# Power_Switch.net
KiCad netlist of a schematic drawn in Altium Designer
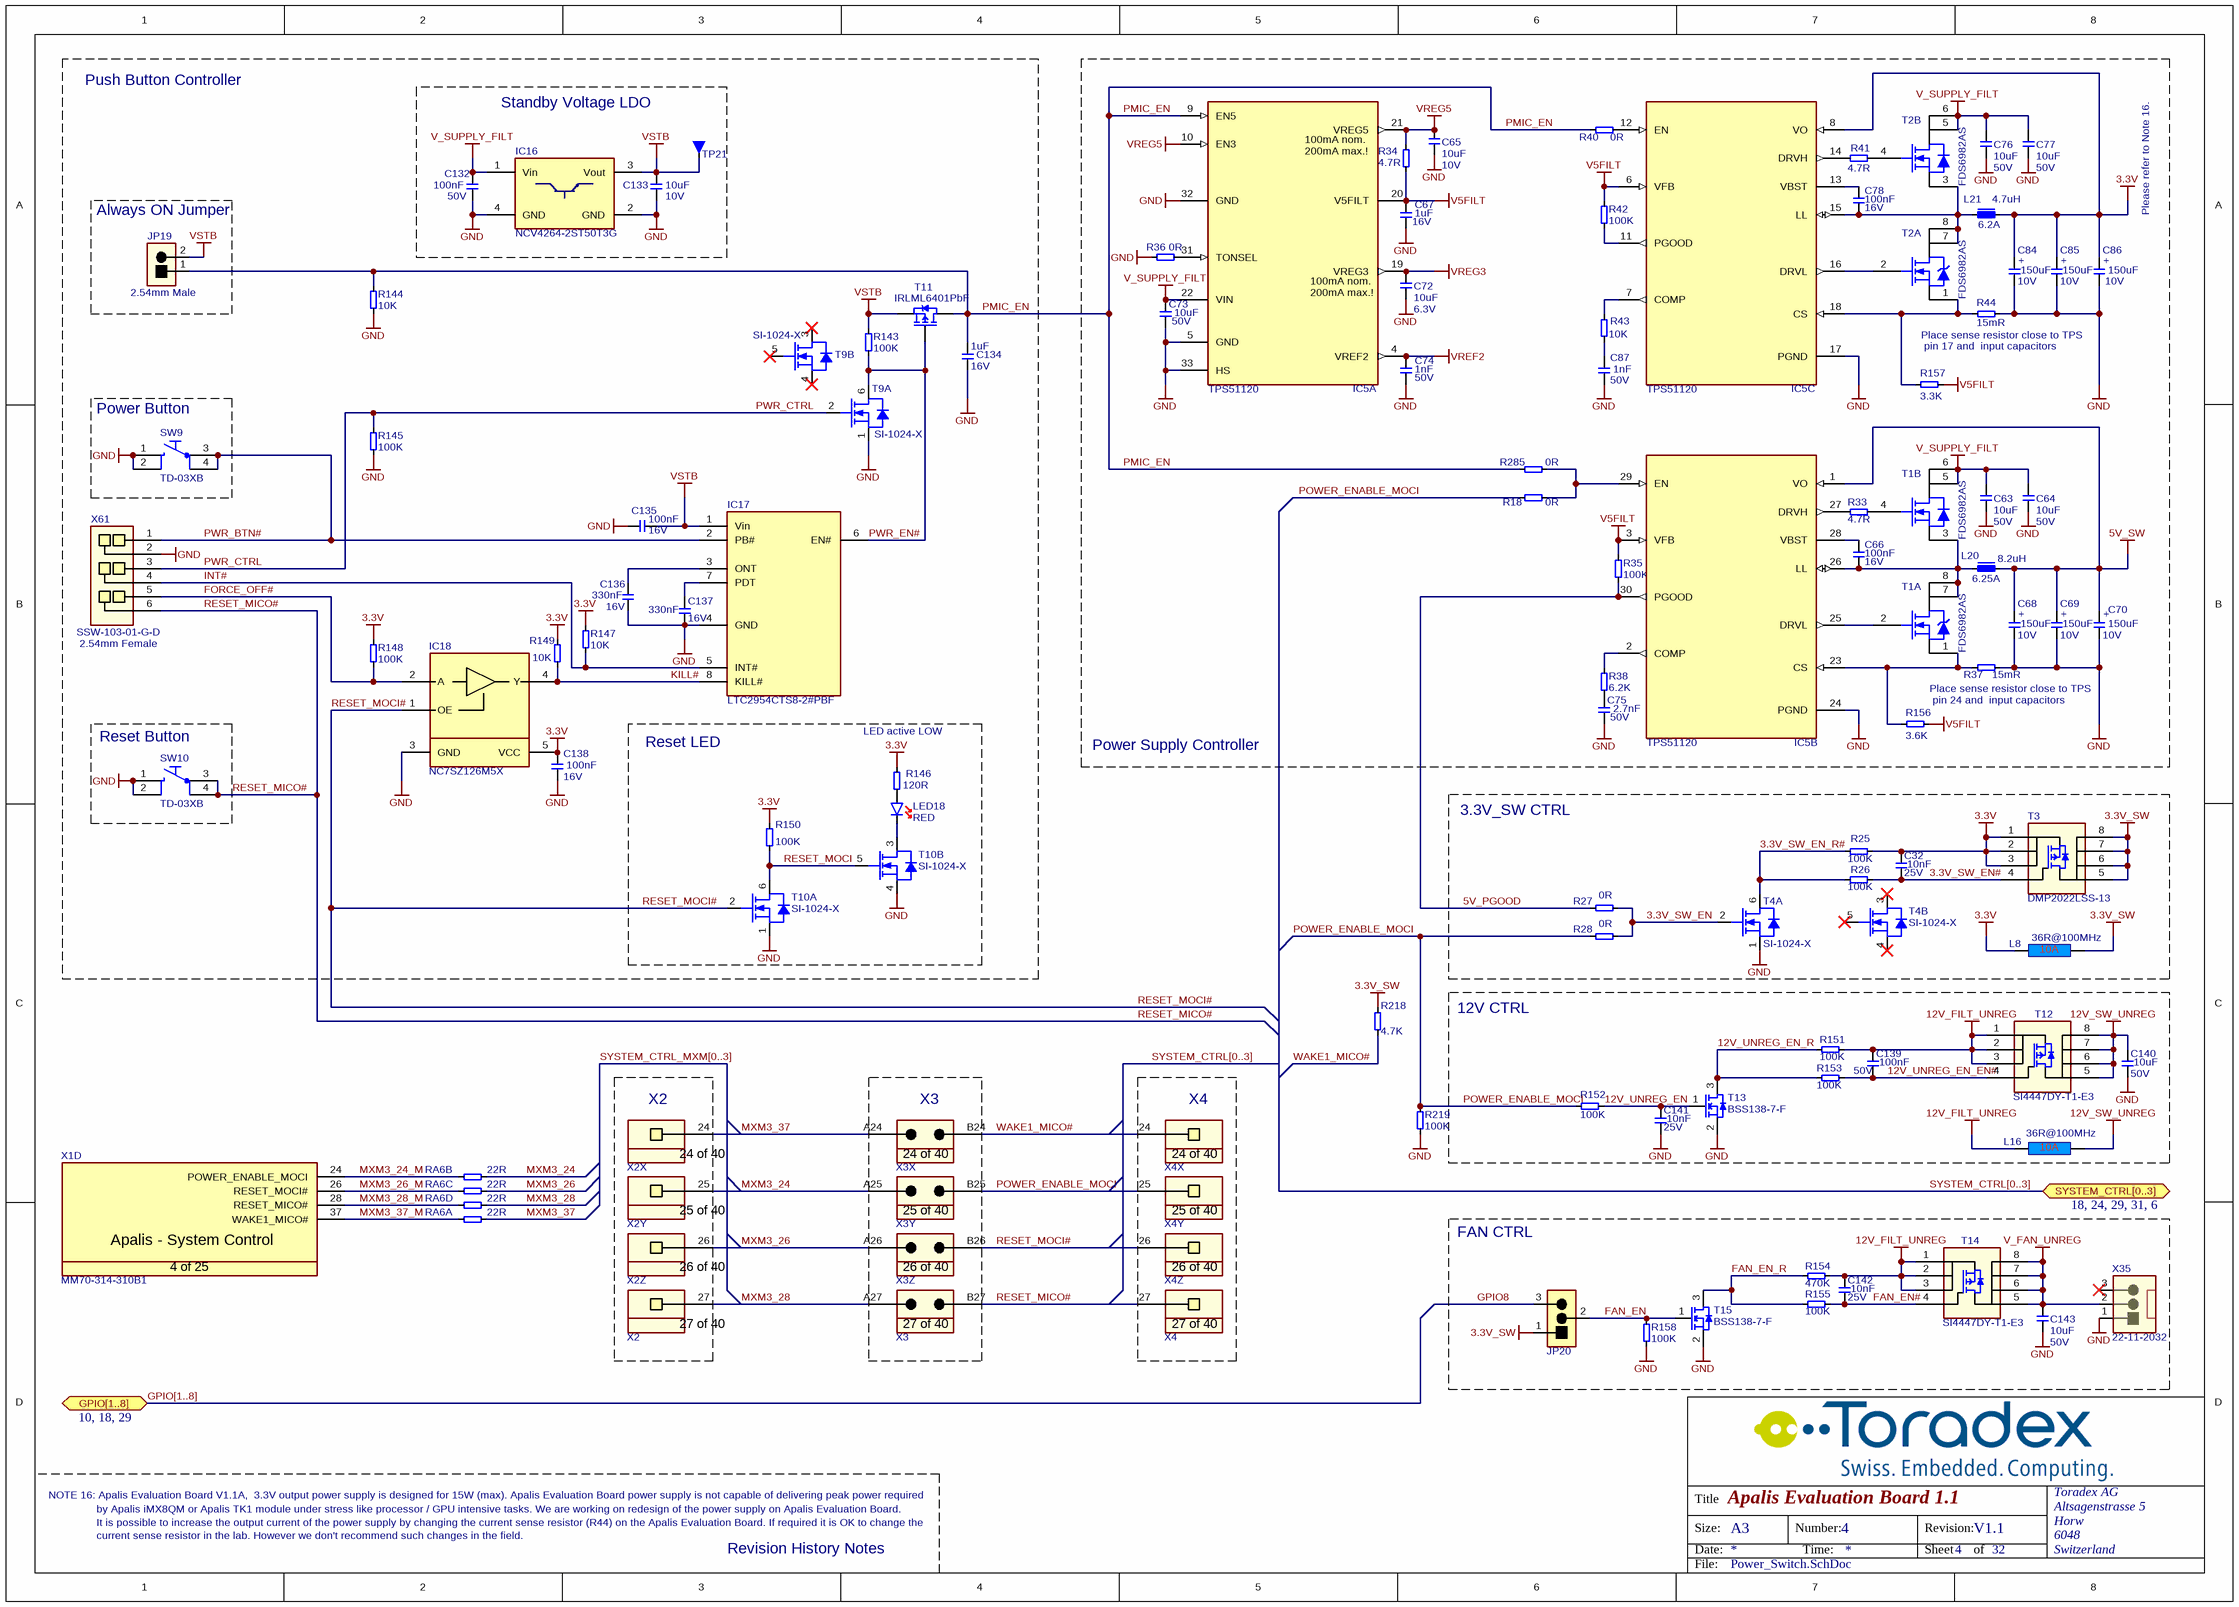
[diagram p0: Power_Switch.SchDoc]

(export (version "E")
  (design (tool "Eeschema 10.0.6"))
  (components
    (comp (ref "C32")
      (value "10nF")
      (footprint "T_CAPC0603X33N")
      (description "Capacitor Ceramic X7R 10nF 25V 10% 0603")
      (fields (field (name "TOLERANCE") "10%") (field (name "RATING") "25V"))
      (libsource (lib "Apalis Evaluation Board") (part "C-X7R-10nF-25V-10%-0603"))
    )
    (comp (ref "C63")
      (value "10uF")
      (footprint "CAPC3225X160N")
      (description "Capacitor Ceramic X5R 10uF 50V 20% 1210")
      (fields (field (name "TOLERANCE") "20%") (field (name "RATING") "50V"))
      (libsource (lib "Apalis Evaluation Board") (part "C-X5R-10uF-50V-20%-1210"))
    )
    (comp (ref "C64")
      (value "10uF")
      (footprint "CAPC3225X160N")
      (description "Capacitor Ceramic X5R 10uF 50V 20% 1210")
      (fields (field (name "TOLERANCE") "20%") (field (name "RATING") "50V"))
      (libsource (lib "Apalis Evaluation Board") (part "C-X5R-10uF-50V-20%-1210"))
    )
    (comp (ref "C65")
      (value "10uF")
      (footprint "T_CAPC0805X125N")
      (description "Capacitor Ceramic X5R 10uF 10V 20% 0805")
      (fields (field (name "TOLERANCE") "20%") (field (name "RATING") "10V"))
      (libsource (lib "Apalis Evaluation Board") (part "C-X5R-10uF-10V-20%-0805"))
    )
    (comp (ref "C66")
      (value "100nF")
      (footprint "T_CAPC0603X33N")
      (description "Capacitor Ceramic X7R 100nF 16V 10% 0603")
      (fields (field (name "TOLERANCE") "10%") (field (name "RATING") "16V"))
      (libsource (lib "Apalis Evaluation Board") (part "C-X7R-100nF-16V-10%-0603"))
    )
    (comp (ref "C67")
      (value "1uF")
      (footprint "T_CAPC0603X33N")
      (description "Capacitor Ceramic X5R 1uF 16V 20% 0603")
      (fields (field (name "TOLERANCE") "20%") (field (name "RATING") "16V"))
      (libsource (lib "Apalis Evaluation Board") (part "C-X5R-1uF-16V-20%-0603"))
    )
    (comp (ref "C68")
      (value "150uF")
      (footprint "CAPMP7343X310N")
      (description "Capacitor TA 150uF 10V 10% 7343")
      (fields (field (name "TOLERANCE") "10%") (field (name "RATING") "10V"))
      (libsource (lib "Apalis Evaluation Board") (part "C-TA-150uF-10V-10%-7343"))
    )
    (comp (ref "C69")
      (value "150uF")
      (footprint "CAPMP7343X310N")
      (description "Capacitor TA 150uF 10V 10% 7343")
      (fields (field (name "TOLERANCE") "10%") (field (name "RATING") "10V"))
      (libsource (lib "Apalis Evaluation Board") (part "C-TA-150uF-10V-10%-7343"))
    )
    (comp (ref "C70")
      (value "150uF")
      (footprint "CAPMP7343X310N")
      (description "Capacitor TA 150uF 10V 10% 7343")
      (fields (field (name "TOLERANCE") "10%") (field (name "RATING") "10V"))
      (libsource (lib "Apalis Evaluation Board") (part "C-TA-150uF-10V-10%-7343"))
    )
    (comp (ref "C72")
      (value "10uF")
      (footprint "T_CAPC0603X33N")
      (description "Capacitor Ceramic X5R 10uF 6.3V 20% 0603")
      (fields (field (name "TOLERANCE") "20%") (field (name "RATING") "6.3V"))
      (libsource (lib "Apalis Evaluation Board") (part "C-X5R-10uF-6.3V-20%-0603"))
    )
    (comp (ref "C73")
      (value "10uF")
      (footprint "CAPC3225X160N")
      (description "Capacitor Ceramic X5R 10uF 50V 20% 1210")
      (fields (field (name "TOLERANCE") "20%") (field (name "RATING") "50V"))
      (libsource (lib "Apalis Evaluation Board") (part "C-X5R-10uF-50V-20%-1210"))
    )
    (comp (ref "C74")
      (value "1nF")
      (footprint "T_CAPC0603X33N")
      (description "Capacitor Ceramic X7R 1nF 50V 10% 0603")
      (fields (field (name "TOLERANCE") "10%") (field (name "RATING") "50V"))
      (libsource (lib "Apalis Evaluation Board") (part "C-X7R-1nF-50V-10%-0603"))
    )
    (comp (ref "C75")
      (value "2.7nF")
      (footprint "CAPC1005X60N")
      (description "Capacitor Ceramic X7R 2.7nF 50V 10% 0402")
      (fields (field (name "TOLERANCE") "10%") (field (name "RATING") "50V"))
      (libsource (lib "Apalis Evaluation Board") (part "C-X7R-2.7nF-50V-10%-0402"))
    )
    (comp (ref "C76")
      (value "10uF")
      (footprint "CAPC3225X160N")
      (description "Capacitor Ceramic X5R 10uF 50V 20% 1210")
      (fields (field (name "TOLERANCE") "20%") (field (name "RATING") "50V"))
      (libsource (lib "Apalis Evaluation Board") (part "C-X5R-10uF-50V-20%-1210"))
    )
    (comp (ref "C77")
      (value "10uF")
      (footprint "CAPC3225X160N")
      (description "Capacitor Ceramic X5R 10uF 50V 20% 1210")
      (fields (field (name "TOLERANCE") "20%") (field (name "RATING") "50V"))
      (libsource (lib "Apalis Evaluation Board") (part "C-X5R-10uF-50V-20%-1210"))
    )
    (comp (ref "C78")
      (value "100nF")
      (footprint "T_CAPC0603X33N")
      (description "Capacitor Ceramic X7R 100nF 16V 10% 0603")
      (fields (field (name "TOLERANCE") "10%") (field (name "RATING") "16V"))
      (libsource (lib "Apalis Evaluation Board") (part "C-X7R-100nF-16V-10%-0603"))
    )
    (comp (ref "C84")
      (value "150uF")
      (footprint "CAPMP7343X310N")
      (description "Capacitor TA 150uF 10V 10% 7343")
      (fields (field (name "TOLERANCE") "10%") (field (name "RATING") "10V"))
      (libsource (lib "Apalis Evaluation Board") (part "C-TA-150uF-10V-10%-7343"))
    )
    (comp (ref "C85")
      (value "150uF")
      (footprint "CAPMP7343X310N")
      (description "Capacitor TA 150uF 10V 10% 7343")
      (fields (field (name "TOLERANCE") "10%") (field (name "RATING") "10V"))
      (libsource (lib "Apalis Evaluation Board") (part "C-TA-150uF-10V-10%-7343"))
    )
    (comp (ref "C86")
      (value "150uF")
      (footprint "CAPMP7343X310N")
      (description "Capacitor TA 150uF 10V 10% 7343")
      (fields (field (name "TOLERANCE") "10%") (field (name "RATING") "10V"))
      (libsource (lib "Apalis Evaluation Board") (part "C-TA-150uF-10V-10%-7343"))
    )
    (comp (ref "C87")
      (value "1nF")
      (footprint "T_CAPC0603X33N")
      (description "Capacitor Ceramic X7R 1nF 50V 10% 0603")
      (fields (field (name "TOLERANCE") "10%") (field (name "RATING") "50V"))
      (libsource (lib "Apalis Evaluation Board") (part "C-X7R-1nF-50V-10%-0603"))
    )
    (comp (ref "C132")
      (value "100nF")
      (footprint "T_CAPC0603X33N")
      (description "Capacitor Ceramic X7R 100nF 50V 20% 0603")
      (fields (field (name "TOLERANCE") "20%") (field (name "RATING") "50V"))
      (libsource (lib "Apalis Evaluation Board") (part "C-X7R-100nF-50V-20%-0603"))
    )
    (comp (ref "C133")
      (value "10uF")
      (footprint "T_CAPC0805X125N")
      (description "Capacitor Ceramic X5R 10uF 10V 20% 0805")
      (fields (field (name "TOLERANCE") "20%") (field (name "RATING") "10V"))
      (libsource (lib "Apalis Evaluation Board") (part "C-X5R-10uF-10V-20%-0805"))
    )
    (comp (ref "C134")
      (value "1uF")
      (footprint "T_CAPC0603X33N")
      (description "Capacitor Ceramic X5R 1uF 16V 20% 0603")
      (fields (field (name "TOLERANCE") "20%") (field (name "RATING") "16V"))
      (libsource (lib "Apalis Evaluation Board") (part "C-X5R-1uF-16V-20%-0603"))
    )
    (comp (ref "C135")
      (value "100nF")
      (footprint "T_CAPC0603X33N")
      (description "Capacitor Ceramic X7R 100nF 16V 10% 0603")
      (fields (field (name "TOLERANCE") "10%") (field (name "RATING") "16V"))
      (libsource (lib "Apalis Evaluation Board") (part "C-X7R-100nF-16V-10%-0603"))
    )
    (comp (ref "C136")
      (value "330nF")
      (footprint "T_CAPC0805X125N")
      (description "Capacitor Ceramic X7R 330nF 16V 10% 0805")
      (fields (field (name "TOLERANCE") "10%") (field (name "RATING") "16V"))
      (libsource (lib "Apalis Evaluation Board") (part "C-X7R-330nF-16V-10%-0805"))
    )
    (comp (ref "C137")
      (value "330nF")
      (footprint "T_CAPC0805X125N")
      (description "Capacitor Ceramic X7R 330nF 16V 10% 0805")
      (fields (field (name "TOLERANCE") "10%") (field (name "RATING") "16V"))
      (libsource (lib "Apalis Evaluation Board") (part "C-X7R-330nF-16V-10%-0805"))
    )
    (comp (ref "C138")
      (value "100nF")
      (footprint "T_CAPC0603X33N")
      (description "Capacitor Ceramic X7R 100nF 16V 10% 0603")
      (fields (field (name "TOLERANCE") "10%") (field (name "RATING") "16V"))
      (libsource (lib "Apalis Evaluation Board") (part "C-X7R-100nF-16V-10%-0603"))
    )
    (comp (ref "C139")
      (value "100nF")
      (footprint "T_CAPC0603X33N")
      (description "Capacitor Ceramic X7R 100nF 50V 20% 0603")
      (fields (field (name "TOLERANCE") "20%") (field (name "RATING") "50V"))
      (libsource (lib "Apalis Evaluation Board") (part "C-X7R-100nF-50V-20%-0603"))
    )
    (comp (ref "C140")
      (value "10uF")
      (footprint "CAPC3225X160N")
      (description "Capacitor Ceramic X5R 10uF 50V 20% 1210")
      (fields (field (name "TOLERANCE") "20%") (field (name "RATING") "50V"))
      (libsource (lib "Apalis Evaluation Board") (part "C-X5R-10uF-50V-20%-1210"))
    )
    (comp (ref "C141")
      (value "10nF")
      (footprint "T_CAPC0603X33N")
      (description "Capacitor Ceramic X7R 10nF 25V 10% 0603")
      (fields (field (name "TOLERANCE") "10%") (field (name "RATING") "25V"))
      (libsource (lib "Apalis Evaluation Board") (part "C-X7R-10nF-25V-10%-0603"))
    )
    (comp (ref "C142")
      (value "10nF")
      (footprint "T_CAPC0603X33N")
      (description "Capacitor Ceramic X7R 10nF 25V 10% 0603")
      (fields (field (name "TOLERANCE") "10%") (field (name "RATING") "25V"))
      (libsource (lib "Apalis Evaluation Board") (part "C-X7R-10nF-25V-10%-0603"))
    )
    (comp (ref "C143")
      (value "10uF")
      (footprint "CAPC3225X160N")
      (description "Capacitor Ceramic X5R 10uF 50V 20% 1210")
      (fields (field (name "TOLERANCE") "20%") (field (name "RATING") "50V"))
      (libsource (lib "Apalis Evaluation Board") (part "C-X5R-10uF-50V-20%-1210"))
    )
    (comp (ref "IC5")
      (value "TPS51120")
      (footprint "QFN50P500X500X100-33N")
      (description "Power Supply Controller")
      (fields (field (name "MANUFACTURER PART NO.") "TPS51120"))
      (libsource (lib "Apalis Evaluation Board") (part "IC-TI-TPS51120"))
    )
    (comp (ref "IC16")
      (value "NCV4264-2ST50T3G")
      (footprint "T_ON_NCV4264-2ST50T3G")
      (description "NCV4264-2ST50T3G LDO Regulator")
      (fields (field (name "MANUFACTURER PART NO.") "NCV4264-2ST50T3G"))
      (libsource (lib "Apalis Evaluation Board") (part "IC-ON-NCV4264-2ST50T3G"))
    )
    (comp (ref "IC17")
      (value "LTC2954CTS8-2#PBF")
      (footprint "T_LINEAR_LTC2954CTS8-2#PBF")
      (description "Push Button On/Off Controller")
      (fields (field (name "MANUFACTURER PART NO.") "LTC2954CTS8-2#PBF"))
      (libsource (lib "Apalis Evaluation Board") (part "IC-LIN-LTC2954CTS8-2#PBF"))
    )
    (comp (ref "IC18")
      (value "NC7SZ126M5X")
      (footprint "SOT95P279X142-5N")
      (description "NC7SZ126M5X  Buffer Three-State Output")
      (fields (field (name "MANUFACTURER PART NO.") "NC7SZ126M5X"))
      (libsource (lib "Apalis Evaluation Board") (part "IC-FAR-NC7SZ126M5X"))
    )
    (comp (ref "JP19")
      (value "TSW-101-07-G-D")
      (footprint "T_Samtec_TSW-101-07-G-D")
      (description "Header male, 1x2 Pins, 2.54 mm pitch")
      (libsource (lib "Apalis Evaluation Board") (part "CON-Samtec-TSW-101-07-G-D"))
    )
    (comp (ref "JP20")
      (value "826936-3")
      (footprint "T_TYCO_826936-3")
      (description "Jumper, 3-Pin")
      (libsource (lib "Apalis Evaluation Board") (part "CON-Tyco-826936-3-1X3-2.54mm-JP_1"))
    )
    (comp (ref "L8")
      (value "36R@100MHz")
      (footprint "T_Laird_35F0121-0SR-10")
      (description "Power Supply FB 10A")
      (fields (field (name "TOLERANCE") "25%"))
      (libsource (lib "Apalis Evaluation Board") (part "L-Laird-35F0121-0SR-10-10A-25%"))
    )
    (comp (ref "L16")
      (value "36R@100MHz")
      (footprint "T_Laird_35F0121-0SR-10")
      (description "Power Supply FB 10A")
      (fields (field (name "TOLERANCE") "25%"))
      (libsource (lib "Apalis Evaluation Board") (part "L-Laird-35F0121-0SR-10-10A-25%"))
    )
    (comp (ref "L20")
      (value "8.2uH")
      (footprint "T_INDM120120X80N")
      (description "Inductance 8.2uH 6.25A 20%")
      (fields
        (field (name "TOLERANCE") "20%")
        (field (name "MANUFACTURER PART NO.") "744771008")
        (field (name "RATING") "6.25A")
      )
      (libsource (lib "Apalis Evaluation Board") (part "L-Wurth-744771008-8.2uH-6.25A-20%"))
    )
    (comp (ref "L21")
      (value "4.7uH")
      (footprint "T_INDM102102X45N")
      (description "Inductance 4.7uH 6.2A 20%")
      (fields
        (field (name "TOLERANCE") "20%")
        (field (name "MANUFACTURER PART NO.") "7447797470")
        (field (name "RATING") "6.2A")
      )
      (libsource (lib "Apalis Evaluation Board") (part "L-Wurth-7447797470-4.7uH-6.2A-20%"))
    )
    (comp (ref "LED18")
      (value "LS T670-K1L2-1")
      (footprint "T_Osram_T670_RED")
      (description "LED red, Osram LS T670-K1L2-1")
      (fields (field (name "COLOR") "RED"))
      (libsource (lib "Apalis Evaluation Board") (part "LED-Osram-LS T670-K1L2-1"))
    )
    (comp (ref "R18")
      (value "0R")
      (footprint "T_RESC0603X30N")
      (description "Resistor 0 ohm 63mW 1% 0603")
      (fields (field (name "TOLERANCE") "1%"))
      (libsource (lib "Apalis Evaluation Board") (part "R-0R-63mW-1%-0603"))
    )
    (comp (ref "R25")
      (value "100K")
      (footprint "T_RESC0603X30N")
      (description "Resistor 100 Kohm 63mW 5% 0603")
      (fields (field (name "TOLERANCE") "5%"))
      (libsource (lib "") (part "R-100KR-63mW-5%-0603_1"))
    )
    (comp (ref "R26")
      (value "100K")
      (footprint "T_RESC0603X30N")
      (description "Resistor 100 Kohm 63mW 5% 0603")
      (fields (field (name "TOLERANCE") "5%"))
      (libsource (lib "") (part "R-100KR-63mW-5%-0603_1"))
    )
    (comp (ref "R27")
      (value "0R")
      (footprint "T_RESC0603X30N")
      (description "Resistor 0 ohm 63mW 1% 0603")
      (fields (field (name "TOLERANCE") "1%"))
      (libsource (lib "Apalis Evaluation Board") (part "R-0R-63mW-1%-0603"))
    )
    (comp (ref "R28")
      (value "0R")
      (footprint "T_RESC0603X30N")
      (description "Resistor 0 ohm 63mW 1% 0603")
      (fields (field (name "TOLERANCE") "1%"))
      (libsource (lib "Apalis Evaluation Board") (part "R-0R-63mW-1%-0603"))
    )
    (comp (ref "R33")
      (value "4.7R")
      (footprint "RESC1005X40N")
      (description "Resistor 4.7 ohm 63mW 5% 0402")
      (fields (field (name "TOLERANCE") "5%"))
      (libsource (lib "Apalis Evaluation Board") (part "R-4.7R-63mW-5%-0402"))
    )
    (comp (ref "R34")
      (value "4.7R")
      (footprint "RESC1005X40N")
      (description "Resistor 4.7 ohm 63mW 5% 0402")
      (fields (field (name "TOLERANCE") "5%"))
      (libsource (lib "Apalis Evaluation Board") (part "R-4.7R-63mW-5%-0402"))
    )
    (comp (ref "R35")
      (value "100K")
      (footprint "T_RESC0603X30N")
      (description "Resistor 100 Kohm 63mW 5% 0603")
      (fields (field (name "TOLERANCE") "5%"))
      (libsource (lib "") (part "R-100KR-63mW-5%-0603_1"))
    )
    (comp (ref "R36")
      (value "0R")
      (footprint "T_RESC0603X30N")
      (description "Resistor 0 ohm 63mW 1% 0603")
      (fields (field (name "TOLERANCE") "1%"))
      (libsource (lib "Apalis Evaluation Board") (part "R-0R-63mW-1%-0603"))
    )
    (comp (ref "R37")
      (value "15mR")
      (footprint "RESC3316X76N")
      (description "Resistor 15 mohm 250mW 1% 1206")
      (fields (field (name "TOLERANCE") "1%"))
      (libsource (lib "Apalis Evaluation Board") (part "R-15mR-250mW-1%-1206"))
    )
    (comp (ref "R38")
      (value "6.2K")
      (footprint "RESC1005X40N")
      (description "Resistor 6.2 Kohm 63mW 1% 0402")
      (fields (field (name "TOLERANCE") "1%"))
      (libsource (lib "Apalis Evaluation Board") (part "R-6.2KR-63mW-1%-0402"))
    )
    (comp (ref "R40")
      (value "0R")
      (footprint "T_RESC0603X30N")
      (description "Resistor 0 ohm 63mW 1% 0603")
      (fields (field (name "TOLERANCE") "1%"))
      (libsource (lib "Apalis Evaluation Board") (part "R-0R-63mW-1%-0603"))
    )
    (comp (ref "R41")
      (value "4.7R")
      (footprint "RESC1005X40N")
      (description "Resistor 4.7 ohm 63mW 5% 0402")
      (fields (field (name "TOLERANCE") "5%"))
      (libsource (lib "Apalis Evaluation Board") (part "R-4.7R-63mW-5%-0402"))
    )
    (comp (ref "R42")
      (value "100K")
      (footprint "T_RESC0603X30N")
      (description "Resistor 100 Kohm 63mW 5% 0603")
      (fields (field (name "TOLERANCE") "5%"))
      (libsource (lib "") (part "R-100KR-63mW-5%-0603_1"))
    )
    (comp (ref "R43")
      (value "10K")
      (footprint "RESC1005X40N")
      (description "Resistor 10 Kohm 63mW 1% 0402")
      (fields (field (name "TOLERANCE") "1%"))
      (libsource (lib "Apalis Evaluation Board") (part "R-10KR-63mW-1%-0402"))
    )
    (comp (ref "R44")
      (value "15mR")
      (footprint "RESC3316X76N")
      (description "Resistor 15 mohm 250mW 1% 1206")
      (fields (field (name "TOLERANCE") "1%"))
      (libsource (lib "Apalis Evaluation Board") (part "R-15mR-250mW-1%-1206"))
    )
    (comp (ref "R143")
      (value "100K")
      (footprint "T_RESC0603X30N")
      (description "Resistor 100 Kohm 63mW 5% 0603")
      (fields (field (name "TOLERANCE") "5%"))
      (libsource (lib "") (part "R-100KR-63mW-5%-0603_1"))
    )
    (comp (ref "R144")
      (value "10K")
      (footprint "T_RESC0603X30N")
      (description "Resistor 10 Kohm 63mW 5% 0603")
      (fields (field (name "TOLERANCE") "5%"))
      (libsource (lib "Apalis Evaluation Board") (part "R-10KR-63mW-5%-0603"))
    )
    (comp (ref "R145")
      (value "100K")
      (footprint "T_RESC0603X30N")
      (description "Resistor 100 Kohm 63mW 5% 0603")
      (fields (field (name "TOLERANCE") "5%"))
      (libsource (lib "") (part "R-100KR-63mW-5%-0603_1"))
    )
    (comp (ref "R146")
      (value "120R")
      (footprint "T_RESC0603X30N")
      (description "Resistor 120 ohm 63mW 5% 0603")
      (fields (field (name "TOLERANCE") "5%"))
      (libsource (lib "Apalis Evaluation Board") (part "R-120R-63mW-5%-0603"))
    )
    (comp (ref "R147")
      (value "10K")
      (footprint "T_RESC0603X30N")
      (description "Resistor 10 Kohm 63mW 5% 0603")
      (fields (field (name "TOLERANCE") "5%"))
      (libsource (lib "Apalis Evaluation Board") (part "R-10KR-63mW-5%-0603"))
    )
    (comp (ref "R148")
      (value "100K")
      (footprint "T_RESC0603X30N")
      (description "Resistor 100 Kohm 63mW 5% 0603")
      (fields (field (name "TOLERANCE") "5%"))
      (libsource (lib "") (part "R-100KR-63mW-5%-0603_1"))
    )
    (comp (ref "R149")
      (value "10K")
      (footprint "T_RESC0603X30N")
      (description "Resistor 10 Kohm 63mW 5% 0603")
      (fields (field (name "TOLERANCE") "5%"))
      (libsource (lib "Apalis Evaluation Board") (part "R-10KR-63mW-5%-0603"))
    )
    (comp (ref "R150")
      (value "100K")
      (footprint "T_RESC0603X30N")
      (description "Resistor 100 Kohm 63mW 5% 0603")
      (fields (field (name "TOLERANCE") "5%"))
      (libsource (lib "") (part "R-100KR-63mW-5%-0603_1"))
    )
    (comp (ref "R151")
      (value "100K")
      (footprint "T_RESC0603X30N")
      (description "Resistor 100 Kohm 63mW 5% 0603")
      (fields (field (name "TOLERANCE") "5%"))
      (libsource (lib "") (part "R-100KR-63mW-5%-0603_1"))
    )
    (comp (ref "R152")
      (value "100K")
      (footprint "T_RESC0603X30N")
      (description "Resistor 100 Kohm 63mW 5% 0603")
      (fields (field (name "TOLERANCE") "5%"))
      (libsource (lib "") (part "R-100KR-63mW-5%-0603_1"))
    )
    (comp (ref "R153")
      (value "100K")
      (footprint "T_RESC0603X30N")
      (description "Resistor 100 Kohm 63mW 5% 0603")
      (fields (field (name "TOLERANCE") "5%"))
      (libsource (lib "") (part "R-100KR-63mW-5%-0603_1"))
    )
    (comp (ref "R154")
      (value "470K")
      (footprint "T_RESC0603X30N")
      (description "Resistor 470 Kohm 63mW 5% 0603")
      (fields (field (name "TOLERANCE") "5%"))
      (libsource (lib "Apalis Evaluation Board") (part "R-470KR-63mW-5%-0603"))
    )
    (comp (ref "R155")
      (value "100K")
      (footprint "T_RESC0603X30N")
      (description "Resistor 100 Kohm 63mW 5% 0603")
      (fields (field (name "TOLERANCE") "5%"))
      (libsource (lib "") (part "R-100KR-63mW-5%-0603_1"))
    )
    (comp (ref "R156")
      (value "3.6K")
      (footprint "T_RESC0603X30N")
      (description "Resistor 3.6 Kohm 63mW 1% 0603")
      (fields (field (name "TOLERANCE") "1%"))
      (libsource (lib "Apalis Evaluation Board") (part "R-3.6KR-63mW-1%-0603"))
    )
    (comp (ref "R157")
      (value "3.3K")
      (footprint "T_RESC0603X30N")
      (description "Resistor 3.3 Kohm 63mW 1% 0603")
      (fields (field (name "TOLERANCE") "1%"))
      (libsource (lib "Apalis Evaluation Board") (part "R-3.3KR-63mW-1%-0603"))
    )
    (comp (ref "R158")
      (value "100K")
      (footprint "T_RESC0603X30N")
      (description "Resistor 100 Kohm 63mW 5% 0603")
      (fields (field (name "TOLERANCE") "5%"))
      (libsource (lib "") (part "R-100KR-63mW-5%-0603_1"))
    )
    (comp (ref "R218")
      (value "4.7K")
      (footprint "t_RESC0603X30N")
      (description "Resistor 4.7 Kohm 63mW 5% 0603")
      (fields (field (name "TOLERANCE") "5%"))
      (libsource (lib "Apalis Evaluation Board") (part "R-4.7kR-63mW-5%-0603"))
    )
    (comp (ref "R219")
      (value "100K")
      (footprint "T_RESC0603X30N")
      (description "Resistor 100 Kohm 63mW 5% 0603")
      (fields (field (name "TOLERANCE") "5%"))
      (libsource (lib "Apalis Evaluation Board") (part "R-100KR-63mW-5%-0603"))
    )
    (comp (ref "R285")
      (value "0R")
      (footprint "T_RESC0603X30N")
      (description "Resistor 0 ohm 63mW 1% 0603")
      (fields (field (name "TOLERANCE") "1%"))
      (libsource (lib "Apalis Evaluation Board") (part "R-0R-63mW-1%-0603"))
    )
    (comp (ref "RA6")
      (value "22R")
      (footprint "T_Resistor_Array_X4")
      (description "Resistor Array 22 R 63mW 5% 1206")
      (fields (field (name "TOLERANCE") "5%"))
      (libsource (lib "Apalis Evaluation Board") (part "RA-22R-63mW-5%-1206-div"))
    )
    (comp (ref "SW9")
      (value "TD-03XB")
      (footprint "T_WMF_TD-03XB")
      (description "Push Button")
      (libsource (lib "Apalis Evaluation Board") (part "SW-WMF-TD-03XB"))
    )
    (comp (ref "SW10")
      (value "TD-03XB")
      (footprint "T_WMF_TD-03XB")
      (description "Push Button")
      (libsource (lib "Apalis Evaluation Board") (part "SW-WMF-TD-03XB"))
    )
    (comp (ref "T1")
      (value "FDS6982AS")
      (footprint "SOIC127P600X173-8N")
      (description "N-Channel PowerTrench SyncFET")
      (fields (field (name "MANUFACTURER PART NO.") "FDS6982AS"))
      (libsource (lib "Apalis Evaluation Board") (part "T-Fairchild-FDS6982AS-N"))
    )
    (comp (ref "T2")
      (value "FDS6982AS")
      (footprint "SOIC127P600X173-8N")
      (description "N-Channel PowerTrench SyncFET")
      (fields (field (name "MANUFACTURER PART NO.") "FDS6982AS"))
      (libsource (lib "") (part "T-Fairchild-FDS6982AS-N_1"))
    )
    (comp (ref "T3")
      (value "DMP2022LSS-13")
      (footprint "SOIC127P600X173-8N")
      (description "p-channel MOSFET, DMP2022LSS-13")
      (fields (field (name "MANUFACTURER PART NO.") "DMP2022LSS-13"))
      (libsource (lib "Apalis Evaluation Board") (part "T-Diodes-DMP2022LSS-13-8-SOIC"))
    )
    (comp (ref "T4")
      (value "T-Vishay-SI-1024X-N")
      (footprint "SOTFL50P160X60-6N")
      (description "Dual N-Channel 20V (D-S)  MOSFET")
      (fields (field (name "MANUFACTURER PART NO.") "SI-1024-X"))
      (libsource (lib "Apalis Evaluation Board") (part "T-Vishay-SI-1024X-N"))
    )
    (comp (ref "T9")
      (value "T-Vishay-SI-1024X-N")
      (footprint "SOTFL50P160X60-6N")
      (description "Dual N-Channel 20V (D-S)  MOSFET")
      (fields (field (name "MANUFACTURER PART NO.") "SI-1024-X"))
      (libsource (lib "Apalis Evaluation Board") (part "T-Vishay-SI-1024X-N"))
    )
    (comp (ref "T10")
      (value "T-Vishay-SI-1024X-N")
      (footprint "SOTFL50P160X60-6N")
      (description "Dual N-Channel 20V (D-S)  MOSFET")
      (fields (field (name "MANUFACTURER PART NO.") "SI-1024-X"))
      (libsource (lib "Apalis Evaluation Board") (part "T-Vishay-SI-1024X-N"))
    )
    (comp (ref "T11")
      (value "IRLML6401PbF")
      (footprint "SOT95P237X112-3N")
      (description "p-channel MOSFET, IRLML6401PbF")
      (libsource (lib "Apalis Evaluation Board") (part "T-IR-IRLML6401PbF-SOT-23"))
    )
    (comp (ref "T12")
      (value "SI4447DY-T1-E3")
      (footprint "SOIC127P600X173-8N")
      (description "p-channel MOSFET, SI4447DY-T1-E3")
      (fields (field (name "MANUFACTURER PART NO.") "SI4447DY-T1-E3"))
      (libsource (lib "Apalis Evaluation Board") (part "T-Vishay-SI4447DY-T1-E3"))
    )
    (comp (ref "T13")
      (value "BSS138-7-F")
      (footprint "SOT95P237X112-3N")
      (description "N-channel MOSFET, BSS138-7-F")
      (fields (field (name "MANUFACTURER PART NO.") "BSS138-7-F"))
      (libsource (lib "Apalis Evaluation Board") (part "T-Diodes-BSS138-7-F"))
    )
    (comp (ref "T14")
      (value "SI4447DY-T1-E3")
      (footprint "SOIC127P600X173-8N")
      (description "p-channel MOSFET, SI4447DY-T1-E3")
      (fields (field (name "MANUFACTURER PART NO.") "SI4447DY-T1-E3"))
      (libsource (lib "Apalis Evaluation Board") (part "T-Vishay-SI4447DY-T1-E3"))
    )
    (comp (ref "T15")
      (value "BSS138-7-F")
      (footprint "SOT95P237X112-3N")
      (description "N-channel MOSFET, BSS138-7-F")
      (fields (field (name "MANUFACTURER PART NO.") "BSS138-7-F"))
      (libsource (lib "Apalis Evaluation Board") (part "T-Diodes-BSS138-7-F"))
    )
    (comp (ref "TP21")
      (value "Testpin")
      (footprint "T_TP-THT")
      (description "Testpin TH")
      (libsource (lib "Apalis Evaluation Board") (part "Testpin"))
    )
    (comp (ref "X1")
      (value "CON-JAE-MM70-314-310B1-314-0.5mm")
      (footprint "T_JAE_MM70-314-310B1")
      (description "MXM3 Connector")
      (fields (field (name "MANUFACTURER PART NO.") "MM70-314-310B1"))
      (libsource (lib "Apalis Evaluation Board") (part "CON-JAE-MM70-314-310B1-314-0.5mm"))
    )
    (comp (ref "X2")
      (value "SSW-110-01-G-S")
      (footprint "T_Samtec_SSW-110-01-G-S")
      (description "Receptacle Female Socket 1x40 pin 2.54mm pitch")
      (libsource (lib "Apalis Evaluation Board") (part "CON-Samtec-SSW-110-01-G-S"))
    )
    (comp (ref "X3")
      (value "TSW-110-07-G-D")
      (footprint "T_Samtec_TSW-110-07-G-D")
      (description "Header 2x40 pin 2.54mm pitch")
      (libsource (lib "Apalis Evaluation Board") (part "CON-Samtec-TSW-110-07-G-D"))
    )
    (comp (ref "X4")
      (value "SSW-110-01-G-S")
      (footprint "T_Samtec_SSW-110-01-G-S")
      (description "Receptacle Female Socket 1x40 pin 2.54mm pitch")
      (libsource (lib "") (part "CON-Samtec-SSW-110-01-G-S_1"))
    )
    (comp (ref "X35")
      (value "22-11-2032")
      (footprint "T_MOLEX_22-11-2032")
      (description "Header with Friction Lock")
      (fields (field (name "MANUFACTURER PART NO.") "22-11-2032"))
      (libsource (lib "Apalis Evaluation Board") (part "CON-Molex-22-11-2032"))
    )
    (comp (ref "X61")
      (value "TSW-103-01-G-D")
      (footprint "T_Samtec_SSW-103-01-G-D")
      (description "Receptacle Female Socket, 2x3 Pins, 2.54mm pitch")
      (fields (field (name "MANUFACTURER PART NO.") "SSW-103-01-G-D"))
      (libsource (lib "Apalis Evaluation Board") (part "CON-Samtec-SSW-103-01-G-D"))
    )
  )
  (nets
    (net (code "16") (name "/3.3V_SW_EN") (class "Default")
      (node (ref "R27") (pin "1") (pinfunction "1_1") (pintype "passive"))
      (node (ref "R28") (pin "2") (pinfunction "2_2") (pintype "passive"))
      (node (ref "T4") (pin "2") (pinfunction "G_2") (pintype "passive"))
    )
    (net (code "17") (name "/3.3V_SW_EN#") (class "Default")
      (node (ref "C32") (pin "1") (pinfunction "1_1") (pintype "passive"))
      (node (ref "R26") (pin "1") (pinfunction "1_1") (pintype "passive"))
      (node (ref "T3") (pin "4") (pinfunction "G_4") (pintype "passive"))
    )
    (net (code "18") (name "/3.3V_SW_EN_R#") (class "Default")
      (node (ref "R25") (pin "2") (pinfunction "2_2") (pintype "passive"))
      (node (ref "R26") (pin "2") (pinfunction "2_2") (pintype "passive"))
      (node (ref "T4") (pin "6") (pinfunction "D_6") (pintype "passive"))
    )
    (net (code "19") (name "/5V_PGOOD") (class "Default")
      (node (ref "IC5") (pin "30") (pinfunction "PGOOD_30") (pintype "output"))
      (node (ref "R27") (pin "2") (pinfunction "2_2") (pintype "passive"))
      (node (ref "R35") (pin "1") (pinfunction "1_1") (pintype "passive"))
    )
    (net (code "20") (name "/12V_UNREG_EN") (class "Default")
      (node (ref "C141") (pin "2") (pinfunction "2_2") (pintype "passive"))
      (node (ref "R152") (pin "2") (pinfunction "2_2") (pintype "passive"))
      (node (ref "T13") (pin "1") (pinfunction "1_1") (pintype "passive"))
    )
    (net (code "21") (name "/12V_UNREG_EN_EN#") (class "Default")
      (node (ref "C139") (pin "1") (pinfunction "1_1") (pintype "passive"))
      (node (ref "R153") (pin "2") (pinfunction "2_2") (pintype "passive"))
      (node (ref "T12") (pin "4") (pinfunction "G_4") (pintype "passive"))
    )
    (net (code "22") (name "/12V_UNREG_EN_R") (class "Default")
      (node (ref "R151") (pin "1") (pinfunction "1_1") (pintype "passive"))
      (node (ref "R153") (pin "1") (pinfunction "1_1") (pintype "passive"))
      (node (ref "T13") (pin "3") (pinfunction "3_3") (pintype "passive"))
    )
    (net (code "23") (name "/FAN_EN") (class "Default")
      (node (ref "JP20") (pin "2") (pinfunction "2_2") (pintype "passive"))
      (node (ref "R158") (pin "1") (pinfunction "1_1") (pintype "passive"))
      (node (ref "T15") (pin "1") (pinfunction "1_1") (pintype "passive"))
    )
    (net (code "24") (name "/FAN_EN#") (class "Default")
      (node (ref "C142") (pin "1") (pinfunction "1_1") (pintype "passive"))
      (node (ref "R155") (pin "2") (pinfunction "2_2") (pintype "passive"))
      (node (ref "T14") (pin "4") (pinfunction "G_4") (pintype "passive"))
    )
    (net (code "25") (name "/FAN_EN_R") (class "Default")
      (node (ref "R154") (pin "1") (pinfunction "1_1") (pintype "passive"))
      (node (ref "R155") (pin "1") (pinfunction "1_1") (pintype "passive"))
      (node (ref "T15") (pin "3") (pinfunction "3_3") (pintype "passive"))
    )
    (net (code "26") (name "/FORCE_OFF#") (class "Default")
      (node (ref "IC18") (pin "2") (pinfunction "A_2") (pintype "passive"))
      (node (ref "R148") (pin "1") (pinfunction "1_1") (pintype "passive"))
      (node (ref "X61") (pin "5") (pinfunction "5_5") (pintype "passive"))
    )
    (net (code "27") (name "/GPIO8") (class "Default")
      (node (ref "JP20") (pin "3") (pinfunction "3_3") (pintype "passive"))
    )
    (net (code "29") (name "/INT#") (class "Default")
      (node (ref "IC17") (pin "5") (pinfunction "INT#_5") (pintype "passive"))
      (node (ref "R147") (pin "2") (pinfunction "2_2") (pintype "passive"))
      (node (ref "X61") (pin "4") (pinfunction "4_4") (pintype "passive"))
    )
    (net (code "30") (name "/KILL#") (class "Default")
      (node (ref "IC17") (pin "8") (pinfunction "KILL#_8") (pintype "passive"))
      (node (ref "IC18") (pin "4") (pinfunction "Y_4") (pintype "passive"))
      (node (ref "R149") (pin "2") (pinfunction "2_2") (pintype "passive"))
    )
    (net (code "31") (name "/MXM3_24") (class "Default")
      (node (ref "RA6") (pin "6") (pinfunction "6_6") (pintype "passive"))
      (node (ref "X2") (pin "25") (pinfunction "25_25") (pintype "passive"))
      (node (ref "X3") (pin "A25") (pinfunction "A25_A25") (pintype "passive"))
    )
    (net (code "32") (name "/MXM3_24_M") (class "Default")
      (node (ref "RA6") (pin "2") (pinfunction "2_2") (pintype "passive"))
      (node (ref "X1") (pin "24") (pinfunction "POWER_ENABLE_MOCI_24") (pintype "passive"))
    )
    (net (code "33") (name "/MXM3_26") (class "Default")
      (node (ref "RA6") (pin "7") (pinfunction "7_7") (pintype "passive"))
      (node (ref "X2") (pin "26") (pinfunction "26_26") (pintype "passive"))
      (node (ref "X3") (pin "A26") (pinfunction "A26_A26") (pintype "passive"))
    )
    (net (code "34") (name "/MXM3_26_M") (class "Default")
      (node (ref "RA6") (pin "3") (pinfunction "3_3") (pintype "passive"))
      (node (ref "X1") (pin "26") (pinfunction "RESET_MOCI#_26") (pintype "passive"))
    )
    (net (code "35") (name "/MXM3_28") (class "Default")
      (node (ref "RA6") (pin "8") (pinfunction "8_8") (pintype "passive"))
      (node (ref "X2") (pin "27") (pinfunction "27_27") (pintype "passive"))
      (node (ref "X3") (pin "A27") (pinfunction "A27_A27") (pintype "passive"))
    )
    (net (code "36") (name "/MXM3_28_M") (class "Default")
      (node (ref "RA6") (pin "4") (pinfunction "4_4") (pintype "passive"))
      (node (ref "X1") (pin "28") (pinfunction "RESET_MICO#_28") (pintype "passive"))
    )
    (net (code "37") (name "/MXM3_37") (class "Default")
      (node (ref "RA6") (pin "5") (pinfunction "5_5") (pintype "passive"))
      (node (ref "X2") (pin "24") (pinfunction "24_24") (pintype "passive"))
      (node (ref "X3") (pin "A24") (pinfunction "A24_A24") (pintype "passive"))
    )
    (net (code "38") (name "/MXM3_37_M") (class "Default")
      (node (ref "RA6") (pin "1") (pinfunction "1_1") (pintype "passive"))
      (node (ref "X1") (pin "37") (pinfunction "WAKE1_MICO#_37") (pintype "passive"))
    )
    (net (code "39") (name "/PMIC_EN") (class "Default")
      (node (ref "C134") (pin "2") (pinfunction "2_2") (pintype "passive"))
      (node (ref "IC5") (pin "9") (pinfunction "EN5_9") (pintype "input"))
      (node (ref "JP19") (pin "1") (pinfunction "1_1") (pintype "passive"))
      (node (ref "R144") (pin "2") (pinfunction "2_2") (pintype "passive"))
      (node (ref "R285") (pin "1") (pinfunction "1_1") (pintype "passive"))
      (node (ref "R40") (pin "1") (pinfunction "1_1") (pintype "passive"))
      (node (ref "T11") (pin "3") (pinfunction "3_3") (pintype "passive"))
    )
    (net (code "40") (name "/POWER_ENABLE_MOCI") (class "Default")
      (node (ref "R152") (pin "1") (pinfunction "1_1") (pintype "passive"))
      (node (ref "R18") (pin "1") (pinfunction "1_1") (pintype "passive"))
      (node (ref "R219") (pin "2") (pinfunction "2_2") (pintype "passive"))
      (node (ref "R28") (pin "1") (pinfunction "1_1") (pintype "passive"))
      (node (ref "X3") (pin "B25") (pinfunction "B25_B25") (pintype "passive"))
      (node (ref "X4") (pin "25") (pinfunction "25_25") (pintype "passive"))
    )
    (net (code "41") (name "/PWR_BTN#") (class "Default")
      (node (ref "IC17") (pin "2") (pinfunction "PB#_2") (pintype "passive"))
      (node (ref "SW9") (pin "3") (pinfunction "3_3") (pintype "passive"))
      (node (ref "SW9") (pin "4") (pinfunction "4_4") (pintype "passive"))
      (node (ref "X61") (pin "1") (pinfunction "1_1") (pintype "passive"))
    )
    (net (code "42") (name "/PWR_CTRL") (class "Default")
      (node (ref "R145") (pin "2") (pinfunction "2_2") (pintype "passive"))
      (node (ref "T9") (pin "2") (pinfunction "G_2") (pintype "passive"))
      (node (ref "X61") (pin "3") (pinfunction "3_3") (pintype "passive"))
    )
    (net (code "43") (name "/PWR_EN#") (class "Default")
      (node (ref "IC17") (pin "6") (pinfunction "EN#_6") (pintype "passive"))
      (node (ref "R143") (pin "1") (pinfunction "1_1") (pintype "passive"))
      (node (ref "T11") (pin "1") (pinfunction "1_1") (pintype "passive"))
      (node (ref "T9") (pin "6") (pinfunction "D_6") (pintype "passive"))
    )
    (net (code "44") (name "/RESET_MICO#") (class "Default")
      (node (ref "SW10") (pin "3") (pinfunction "3_3") (pintype "passive"))
      (node (ref "SW10") (pin "4") (pinfunction "4_4") (pintype "passive"))
      (node (ref "X3") (pin "B27") (pinfunction "B27_B27") (pintype "passive"))
      (node (ref "X4") (pin "27") (pinfunction "27_27") (pintype "passive"))
      (node (ref "X61") (pin "6") (pinfunction "6_6") (pintype "passive"))
    )
    (net (code "45") (name "/RESET_MOCI") (class "Default")
      (node (ref "R150") (pin "1") (pinfunction "1_1") (pintype "passive"))
      (node (ref "T10") (pin "5") (pinfunction "G_5") (pintype "passive"))
      (node (ref "T10") (pin "6") (pinfunction "D_6") (pintype "passive"))
    )
    (net (code "46") (name "/RESET_MOCI#") (class "Default")
      (node (ref "IC18") (pin "1") (pinfunction "OE_1") (pintype "passive"))
      (node (ref "T10") (pin "2") (pinfunction "G_2") (pintype "passive"))
      (node (ref "X3") (pin "B26") (pinfunction "B26_B26") (pintype "passive"))
      (node (ref "X4") (pin "26") (pinfunction "26_26") (pintype "passive"))
    )
    (net (code "49") (name "/WAKE1_MICO#") (class "Default")
      (node (ref "R218") (pin "2") (pinfunction "2_2") (pintype "passive"))
      (node (ref "X3") (pin "B24") (pinfunction "B24_B24") (pintype "passive"))
      (node (ref "X4") (pin "24") (pinfunction "24_24") (pintype "passive"))
    )
    (net (code "50") (name "3.3V") (class "Default")
      (node (ref "C138") (pin "1") (pinfunction "1_1") (pintype "passive"))
      (node (ref "C32") (pin "2") (pinfunction "2_2") (pintype "passive"))
      (node (ref "C84") (pin "1") (pinfunction "1_1") (pintype "passive"))
      (node (ref "C85") (pin "1") (pinfunction "1_1") (pintype "passive"))
      (node (ref "C86") (pin "1") (pinfunction "1_1") (pintype "passive"))
      (node (ref "IC18") (pin "5") (pinfunction "VCC_5") (pintype "passive"))
      (node (ref "IC5") (pin "8") (pinfunction "VO_8") (pintype "input"))
      (node (ref "L21") (pin "2") (pinfunction "2_2") (pintype "passive"))
      (node (ref "L8") (pin "1") (pinfunction "1_1") (pintype "passive"))
      (node (ref "R146") (pin "2") (pinfunction "2_2") (pintype "passive"))
      (node (ref "R147") (pin "1") (pinfunction "1_1") (pintype "passive"))
      (node (ref "R148") (pin "2") (pinfunction "2_2") (pintype "passive"))
      (node (ref "R149") (pin "1") (pinfunction "1_1") (pintype "passive"))
      (node (ref "R150") (pin "2") (pinfunction "2_2") (pintype "passive"))
      (node (ref "R25") (pin "1") (pinfunction "1_1") (pintype "passive"))
      (node (ref "T3") (pin "1") (pinfunction "S_1") (pintype "passive"))
      (node (ref "T3") (pin "2") (pinfunction "S_2") (pintype "passive"))
      (node (ref "T3") (pin "3") (pinfunction "S_3") (pintype "passive"))
    )
    (net (code "51") (name "3.3V_SW") (class "Default")
      (node (ref "JP20") (pin "1") (pinfunction "1_1") (pintype "passive"))
      (node (ref "L8") (pin "2") (pinfunction "2_2") (pintype "passive"))
      (node (ref "R218") (pin "1") (pinfunction "1_1") (pintype "passive"))
      (node (ref "T3") (pin "5") (pinfunction "D_5") (pintype "passive"))
      (node (ref "T3") (pin "6") (pinfunction "D_6") (pintype "passive"))
      (node (ref "T3") (pin "7") (pinfunction "D_7") (pintype "passive"))
      (node (ref "T3") (pin "8") (pinfunction "D_8") (pintype "passive"))
    )
    (net (code "52") (name "5V_SW") (class "Default")
      (node (ref "C68") (pin "1") (pinfunction "1_1") (pintype "passive"))
      (node (ref "C69") (pin "1") (pinfunction "1_1") (pintype "passive"))
      (node (ref "C70") (pin "1") (pinfunction "1_1") (pintype "passive"))
      (node (ref "IC5") (pin "1") (pinfunction "VO_1") (pintype "input"))
      (node (ref "L20") (pin "2") (pinfunction "2_2") (pintype "passive"))
    )
    (net (code "53") (name "12V_FILT_UNREG") (class "Default")
      (node (ref "C139") (pin "2") (pinfunction "2_2") (pintype "passive"))
      (node (ref "C142") (pin "2") (pinfunction "2_2") (pintype "passive"))
      (node (ref "L16") (pin "1") (pinfunction "1_1") (pintype "passive"))
      (node (ref "R151") (pin "2") (pinfunction "2_2") (pintype "passive"))
      (node (ref "R154") (pin "2") (pinfunction "2_2") (pintype "passive"))
      (node (ref "T12") (pin "1") (pinfunction "S_1") (pintype "passive"))
      (node (ref "T12") (pin "2") (pinfunction "S_2") (pintype "passive"))
      (node (ref "T12") (pin "3") (pinfunction "S_3") (pintype "passive"))
      (node (ref "T14") (pin "1") (pinfunction "S_1") (pintype "passive"))
      (node (ref "T14") (pin "2") (pinfunction "S_2") (pintype "passive"))
      (node (ref "T14") (pin "3") (pinfunction "S_3") (pintype "passive"))
    )
    (net (code "54") (name "12V_SW_UNREG") (class "Default")
      (node (ref "C140") (pin "2") (pinfunction "2_2") (pintype "passive"))
      (node (ref "L16") (pin "2") (pinfunction "2_2") (pintype "passive"))
      (node (ref "T12") (pin "5") (pinfunction "D_5") (pintype "passive"))
      (node (ref "T12") (pin "6") (pinfunction "D_6") (pintype "passive"))
      (node (ref "T12") (pin "7") (pinfunction "D_7") (pintype "passive"))
      (node (ref "T12") (pin "8") (pinfunction "D_8") (pintype "passive"))
    )
    (net (code "55") (name "GND") (class "Default")
      (node (ref "C132") (pin "1") (pinfunction "1_1") (pintype "passive"))
      (node (ref "C133") (pin "1") (pinfunction "1_1") (pintype "passive"))
      (node (ref "C134") (pin "1") (pinfunction "1_1") (pintype "passive"))
      (node (ref "C135") (pin "1") (pinfunction "1_1") (pintype "passive"))
      (node (ref "C136") (pin "1") (pinfunction "1_1") (pintype "passive"))
      (node (ref "C137") (pin "1") (pinfunction "1_1") (pintype "passive"))
      (node (ref "C138") (pin "2") (pinfunction "2_2") (pintype "passive"))
      (node (ref "C140") (pin "1") (pinfunction "1_1") (pintype "passive"))
      (node (ref "C141") (pin "1") (pinfunction "1_1") (pintype "passive"))
      (node (ref "C143") (pin "1") (pinfunction "1_1") (pintype "passive"))
      (node (ref "C63") (pin "1") (pinfunction "1_1") (pintype "passive"))
      (node (ref "C64") (pin "1") (pinfunction "1_1") (pintype "passive"))
      (node (ref "C65") (pin "1") (pinfunction "1_1") (pintype "passive"))
      (node (ref "C67") (pin "1") (pinfunction "1_1") (pintype "passive"))
      (node (ref "C68") (pin "2") (pinfunction "2_2") (pintype "passive"))
      (node (ref "C69") (pin "2") (pinfunction "2_2") (pintype "passive"))
      (node (ref "C70") (pin "2") (pinfunction "2_2") (pintype "passive"))
      (node (ref "C72") (pin "1") (pinfunction "1_1") (pintype "passive"))
      (node (ref "C73") (pin "1") (pinfunction "1_1") (pintype "passive"))
      (node (ref "C74") (pin "1") (pinfunction "1_1") (pintype "passive"))
      (node (ref "C75") (pin "1") (pinfunction "1_1") (pintype "passive"))
      (node (ref "C76") (pin "1") (pinfunction "1_1") (pintype "passive"))
      (node (ref "C77") (pin "1") (pinfunction "1_1") (pintype "passive"))
      (node (ref "C84") (pin "2") (pinfunction "2_2") (pintype "passive"))
      (node (ref "C85") (pin "2") (pinfunction "2_2") (pintype "passive"))
      (node (ref "C86") (pin "2") (pinfunction "2_2") (pintype "passive"))
      (node (ref "C87") (pin "1") (pinfunction "1_1") (pintype "passive"))
      (node (ref "IC16") (pin "2") (pinfunction "GND_2") (pintype "passive"))
      (node (ref "IC16") (pin "4") (pinfunction "GND_4") (pintype "passive"))
      (node (ref "IC17") (pin "4") (pinfunction "GND_4") (pintype "passive"))
      (node (ref "IC18") (pin "3") (pinfunction "GND_3") (pintype "passive"))
      (node (ref "IC5") (pin "17") (pinfunction "PGND_17") (pintype "power_in"))
      (node (ref "IC5") (pin "24") (pinfunction "PGND_24") (pintype "power_in"))
      (node (ref "IC5") (pin "32") (pinfunction "GND_32") (pintype "power_in"))
      (node (ref "IC5") (pin "33") (pinfunction "HS_33") (pintype "passive"))
      (node (ref "IC5") (pin "5") (pinfunction "GND_5") (pintype "power_in"))
      (node (ref "R144") (pin "1") (pinfunction "1_1") (pintype "passive"))
      (node (ref "R145") (pin "1") (pinfunction "1_1") (pintype "passive"))
      (node (ref "R158") (pin "2") (pinfunction "2_2") (pintype "passive"))
      (node (ref "R219") (pin "1") (pinfunction "1_1") (pintype "passive"))
      (node (ref "R36") (pin "1") (pinfunction "1_1") (pintype "passive"))
      (node (ref "R37") (pin "2") (pinfunction "2_2") (pintype "passive"))
      (node (ref "R44") (pin "2") (pinfunction "2_2") (pintype "passive"))
      (node (ref "SW10") (pin "1") (pinfunction "1_1") (pintype "passive"))
      (node (ref "SW10") (pin "2") (pinfunction "2_2") (pintype "passive"))
      (node (ref "SW9") (pin "1") (pinfunction "1_1") (pintype "passive"))
      (node (ref "SW9") (pin "2") (pinfunction "2_2") (pintype "passive"))
      (node (ref "T10") (pin "1") (pinfunction "S_1") (pintype "passive"))
      (node (ref "T10") (pin "4") (pinfunction "S_4") (pintype "passive"))
      (node (ref "T13") (pin "2") (pinfunction "2_2") (pintype "passive"))
      (node (ref "T15") (pin "2") (pinfunction "2_2") (pintype "passive"))
      (node (ref "T4") (pin "1") (pinfunction "S_1") (pintype "passive"))
      (node (ref "T9") (pin "1") (pinfunction "S_1") (pintype "passive"))
      (node (ref "X35") (pin "1") (pinfunction "1_1") (pintype "passive"))
      (node (ref "X61") (pin "2") (pinfunction "2_2") (pintype "passive"))
    )
    (net (code "56") (name "Net-(C75-Pad2)") (class "Default")
      (node (ref "C75") (pin "2") (pinfunction "2_2") (pintype "passive"))
      (node (ref "R38") (pin "1") (pinfunction "1_1") (pintype "passive"))
    )
    (net (code "57") (name "Net-(C87-Pad2)") (class "Default")
      (node (ref "C87") (pin "2") (pinfunction "2_2") (pintype "passive"))
      (node (ref "R43") (pin "1") (pinfunction "1_1") (pintype "passive"))
    )
    (net (code "58") (name "Net-(IC5A-TONSEL)") (class "Default")
      (node (ref "IC5") (pin "31") (pinfunction "TONSEL_31") (pintype "input"))
      (node (ref "R36") (pin "2") (pinfunction "2_2") (pintype "passive"))
    )
    (net (code "59") (name "Net-(IC5B-COMP)") (class "Default")
      (node (ref "IC5") (pin "2") (pinfunction "COMP_2") (pintype "output"))
      (node (ref "R38") (pin "2") (pinfunction "2_2") (pintype "passive"))
    )
    (net (code "60") (name "Net-(IC5B-CS)") (class "Default")
      (node (ref "IC5") (pin "23") (pinfunction "CS_23") (pintype "input"))
      (node (ref "R156") (pin "1") (pinfunction "1_1") (pintype "passive"))
      (node (ref "R37") (pin "1") (pinfunction "1_1") (pintype "passive"))
      (node (ref "T1") (pin "1") (pinfunction "S_1") (pintype "passive"))
    )
    (net (code "61") (name "Net-(IC5B-DRVH)") (class "Default")
      (node (ref "IC5") (pin "27") (pinfunction "DRVH_27") (pintype "output"))
      (node (ref "R33") (pin "1") (pinfunction "1_1") (pintype "passive"))
    )
    (net (code "62") (name "Net-(IC5B-DRVL)") (class "Default")
      (node (ref "IC5") (pin "25") (pinfunction "DRVL_25") (pintype "output"))
      (node (ref "T1") (pin "2") (pinfunction "G_2") (pintype "passive"))
    )
    (net (code "63") (name "Net-(IC5B-EN)") (class "Default")
      (node (ref "IC5") (pin "29") (pinfunction "EN_29") (pintype "input"))
      (node (ref "R18") (pin "2") (pinfunction "2_2") (pintype "passive"))
      (node (ref "R285") (pin "2") (pinfunction "2_2") (pintype "passive"))
    )
    (net (code "64") (name "Net-(IC5B-LL)") (class "Default")
      (node (ref "C66") (pin "1") (pinfunction "1_1") (pintype "passive"))
      (node (ref "IC5") (pin "26") (pinfunction "LL_26") (pintype "bidirectional"))
      (node (ref "L20") (pin "1") (pinfunction "1_1") (pintype "passive"))
      (node (ref "T1") (pin "3") (pinfunction "S_3") (pintype "passive"))
      (node (ref "T1") (pin "7") (pinfunction "D_7") (pintype "passive"))
      (node (ref "T1") (pin "8") (pinfunction "D_8") (pintype "passive"))
    )
    (net (code "65") (name "Net-(IC5B-VBST)") (class "Default")
      (node (ref "C66") (pin "2") (pinfunction "2_2") (pintype "passive"))
      (node (ref "IC5") (pin "28") (pinfunction "VBST_28") (pintype "power_in"))
    )
    (net (code "66") (name "Net-(IC5C-COMP)") (class "Default")
      (node (ref "IC5") (pin "7") (pinfunction "COMP_7") (pintype "output"))
      (node (ref "R43") (pin "2") (pinfunction "2_2") (pintype "passive"))
    )
    (net (code "67") (name "Net-(IC5C-CS)") (class "Default")
      (node (ref "IC5") (pin "18") (pinfunction "CS_18") (pintype "input"))
      (node (ref "R157") (pin "1") (pinfunction "1_1") (pintype "passive"))
      (node (ref "R44") (pin "1") (pinfunction "1_1") (pintype "passive"))
      (node (ref "T2") (pin "1") (pinfunction "S_1") (pintype "passive"))
    )
    (net (code "68") (name "Net-(IC5C-DRVH)") (class "Default")
      (node (ref "IC5") (pin "14") (pinfunction "DRVH_14") (pintype "output"))
      (node (ref "R41") (pin "1") (pinfunction "1_1") (pintype "passive"))
    )
    (net (code "69") (name "Net-(IC5C-DRVL)") (class "Default")
      (node (ref "IC5") (pin "16") (pinfunction "DRVL_16") (pintype "output"))
      (node (ref "T2") (pin "2") (pinfunction "G_2") (pintype "passive"))
    )
    (net (code "70") (name "Net-(IC5C-EN)") (class "Default")
      (node (ref "IC5") (pin "12") (pinfunction "EN_12") (pintype "input"))
      (node (ref "R40") (pin "2") (pinfunction "2_2") (pintype "passive"))
    )
    (net (code "71") (name "Net-(IC5C-LL)") (class "Default")
      (node (ref "C78") (pin "1") (pinfunction "1_1") (pintype "passive"))
      (node (ref "IC5") (pin "15") (pinfunction "LL_15") (pintype "bidirectional"))
      (node (ref "L21") (pin "1") (pinfunction "1_1") (pintype "passive"))
      (node (ref "T2") (pin "3") (pinfunction "S_3") (pintype "passive"))
      (node (ref "T2") (pin "7") (pinfunction "D_7") (pintype "passive"))
      (node (ref "T2") (pin "8") (pinfunction "D_8") (pintype "passive"))
    )
    (net (code "72") (name "Net-(IC5C-PGOOD)") (class "Default")
      (node (ref "IC5") (pin "11") (pinfunction "PGOOD_11") (pintype "output"))
      (node (ref "R42") (pin "1") (pinfunction "1_1") (pintype "passive"))
    )
    (net (code "73") (name "Net-(IC5C-VBST)") (class "Default")
      (node (ref "C78") (pin "2") (pinfunction "2_2") (pintype "passive"))
      (node (ref "IC5") (pin "13") (pinfunction "VBST_13") (pintype "passive"))
    )
    (net (code "74") (name "Net-(IC17-ONT)") (class "Default")
      (node (ref "C136") (pin "2") (pinfunction "2_2") (pintype "passive"))
      (node (ref "IC17") (pin "3") (pinfunction "ONT_3") (pintype "passive"))
    )
    (net (code "75") (name "Net-(IC17-PDT)") (class "Default")
      (node (ref "C137") (pin "2") (pinfunction "2_2") (pintype "passive"))
      (node (ref "IC17") (pin "7") (pinfunction "PDT_7") (pintype "passive"))
    )
    (net (code "76") (name "Net-(LED18-PadA)") (class "Default")
      (node (ref "LED18") (pin "A") (pinfunction "A_A") (pintype "passive"))
      (node (ref "R146") (pin "1") (pinfunction "1_1") (pintype "passive"))
    )
    (net (code "77") (name "Net-(T1B-G)") (class "Default")
      (node (ref "R33") (pin "2") (pinfunction "2_2") (pintype "passive"))
      (node (ref "T1") (pin "4") (pinfunction "G_4") (pintype "passive"))
    )
    (net (code "78") (name "Net-(T2B-G)") (class "Default")
      (node (ref "R41") (pin "2") (pinfunction "2_2") (pintype "passive"))
      (node (ref "T2") (pin "4") (pinfunction "G_4") (pintype "passive"))
    )
    (net (code "79") (name "Net-(T10B-D)") (class "Default")
      (node (ref "LED18") (pin "K") (pinfunction "K_K") (pintype "passive"))
      (node (ref "T10") (pin "3") (pinfunction "D_3") (pintype "passive"))
    )
    (net (code "80") (name "V5FILT") (class "Default")
      (node (ref "C67") (pin "2") (pinfunction "2_2") (pintype "passive"))
      (node (ref "IC5") (pin "20") (pinfunction "V5FILT_20") (pintype "power_in"))
      (node (ref "IC5") (pin "3") (pinfunction "VFB_3") (pintype "input"))
      (node (ref "IC5") (pin "6") (pinfunction "VFB_6") (pintype "input"))
      (node (ref "R156") (pin "2") (pinfunction "2_2") (pintype "passive"))
      (node (ref "R157") (pin "2") (pinfunction "2_2") (pintype "passive"))
      (node (ref "R34") (pin "1") (pinfunction "1_1") (pintype "passive"))
      (node (ref "R35") (pin "2") (pinfunction "2_2") (pintype "passive"))
      (node (ref "R42") (pin "2") (pinfunction "2_2") (pintype "passive"))
    )
    (net (code "81") (name "VREF2") (class "Default")
      (node (ref "C74") (pin "2") (pinfunction "2_2") (pintype "passive"))
      (node (ref "IC5") (pin "4") (pinfunction "VREF2_4") (pintype "output"))
    )
    (net (code "82") (name "VREG3") (class "Default")
      (node (ref "C72") (pin "2") (pinfunction "2_2") (pintype "passive"))
      (node (ref "IC5") (pin "19") (pinfunction "VREG3_19") (pintype "output"))
    )
    (net (code "83") (name "VREG5") (class "Default")
      (node (ref "C65") (pin "2") (pinfunction "2_2") (pintype "passive"))
      (node (ref "IC5") (pin "10") (pinfunction "EN3_10") (pintype "input"))
      (node (ref "IC5") (pin "21") (pinfunction "VREG5_21") (pintype "output"))
      (node (ref "R34") (pin "2") (pinfunction "2_2") (pintype "passive"))
    )
    (net (code "84") (name "VSTB") (class "Default")
      (node (ref "C133") (pin "2") (pinfunction "2_2") (pintype "passive"))
      (node (ref "C135") (pin "2") (pinfunction "2_2") (pintype "passive"))
      (node (ref "IC16") (pin "3") (pinfunction "Vout_3") (pintype "passive"))
      (node (ref "IC17") (pin "1") (pinfunction "Vin_1") (pintype "passive"))
      (node (ref "JP19") (pin "2") (pinfunction "2_2") (pintype "passive"))
      (node (ref "R143") (pin "2") (pinfunction "2_2") (pintype "passive"))
      (node (ref "T11") (pin "2") (pinfunction "2_2") (pintype "passive"))
      (node (ref "TP21") (pin "1") (pinfunction "1_1") (pintype "passive"))
    )
    (net (code "85") (name "V_FAN_UNREG") (class "Default")
      (node (ref "C143") (pin "2") (pinfunction "2_2") (pintype "passive"))
      (node (ref "T14") (pin "5") (pinfunction "D_5") (pintype "passive"))
      (node (ref "T14") (pin "6") (pinfunction "D_6") (pintype "passive"))
      (node (ref "T14") (pin "7") (pinfunction "D_7") (pintype "passive"))
      (node (ref "T14") (pin "8") (pinfunction "D_8") (pintype "passive"))
      (node (ref "X35") (pin "2") (pinfunction "2_2") (pintype "passive"))
    )
    (net (code "86") (name "V_SUPPLY_FILT") (class "Default")
      (node (ref "C132") (pin "2") (pinfunction "2_2") (pintype "passive"))
      (node (ref "C63") (pin "2") (pinfunction "2_2") (pintype "passive"))
      (node (ref "C64") (pin "2") (pinfunction "2_2") (pintype "passive"))
      (node (ref "C73") (pin "2") (pinfunction "2_2") (pintype "passive"))
      (node (ref "C76") (pin "2") (pinfunction "2_2") (pintype "passive"))
      (node (ref "C77") (pin "2") (pinfunction "2_2") (pintype "passive"))
      (node (ref "IC16") (pin "1") (pinfunction "Vin_1") (pintype "passive"))
      (node (ref "IC5") (pin "22") (pinfunction "VIN_22") (pintype "power_in"))
      (node (ref "T1") (pin "5") (pinfunction "D_5") (pintype "passive"))
      (node (ref "T1") (pin "6") (pinfunction "D_6") (pintype "passive"))
      (node (ref "T2") (pin "5") (pinfunction "D_5") (pintype "passive"))
      (node (ref "T2") (pin "6") (pinfunction "D_6") (pintype "passive"))
    )
    (net (code "87") (name "unconnected-(T4B-D-Pad3)") (class "Default")
      (node (ref "T4") (pin "3") (pinfunction "D_3") (pintype "passive+no_connect"))
    )
    (net (code "88") (name "unconnected-(T4B-G-Pad5)") (class "Default")
      (node (ref "T4") (pin "5") (pinfunction "G_5") (pintype "passive+no_connect"))
    )
    (net (code "89") (name "unconnected-(T4B-S-Pad4)") (class "Default")
      (node (ref "T4") (pin "4") (pinfunction "S_4") (pintype "passive+no_connect"))
    )
    (net (code "90") (name "unconnected-(T9B-D-Pad3)") (class "Default")
      (node (ref "T9") (pin "3") (pinfunction "D_3") (pintype "passive+no_connect"))
    )
    (net (code "91") (name "unconnected-(T9B-G-Pad5)") (class "Default")
      (node (ref "T9") (pin "5") (pinfunction "G_5") (pintype "passive+no_connect"))
    )
    (net (code "92") (name "unconnected-(T9B-S-Pad4)") (class "Default")
      (node (ref "T9") (pin "4") (pinfunction "S_4") (pintype "passive+no_connect"))
    )
    (net (code "93") (name "unconnected-(X35-Pad3)") (class "Default")
      (node (ref "X35") (pin "3") (pinfunction "3_3") (pintype "passive+no_connect"))
    )
  )
)
